# SPI_Backplane.net
KiCad netlist of a schematic drawn in EAGLE
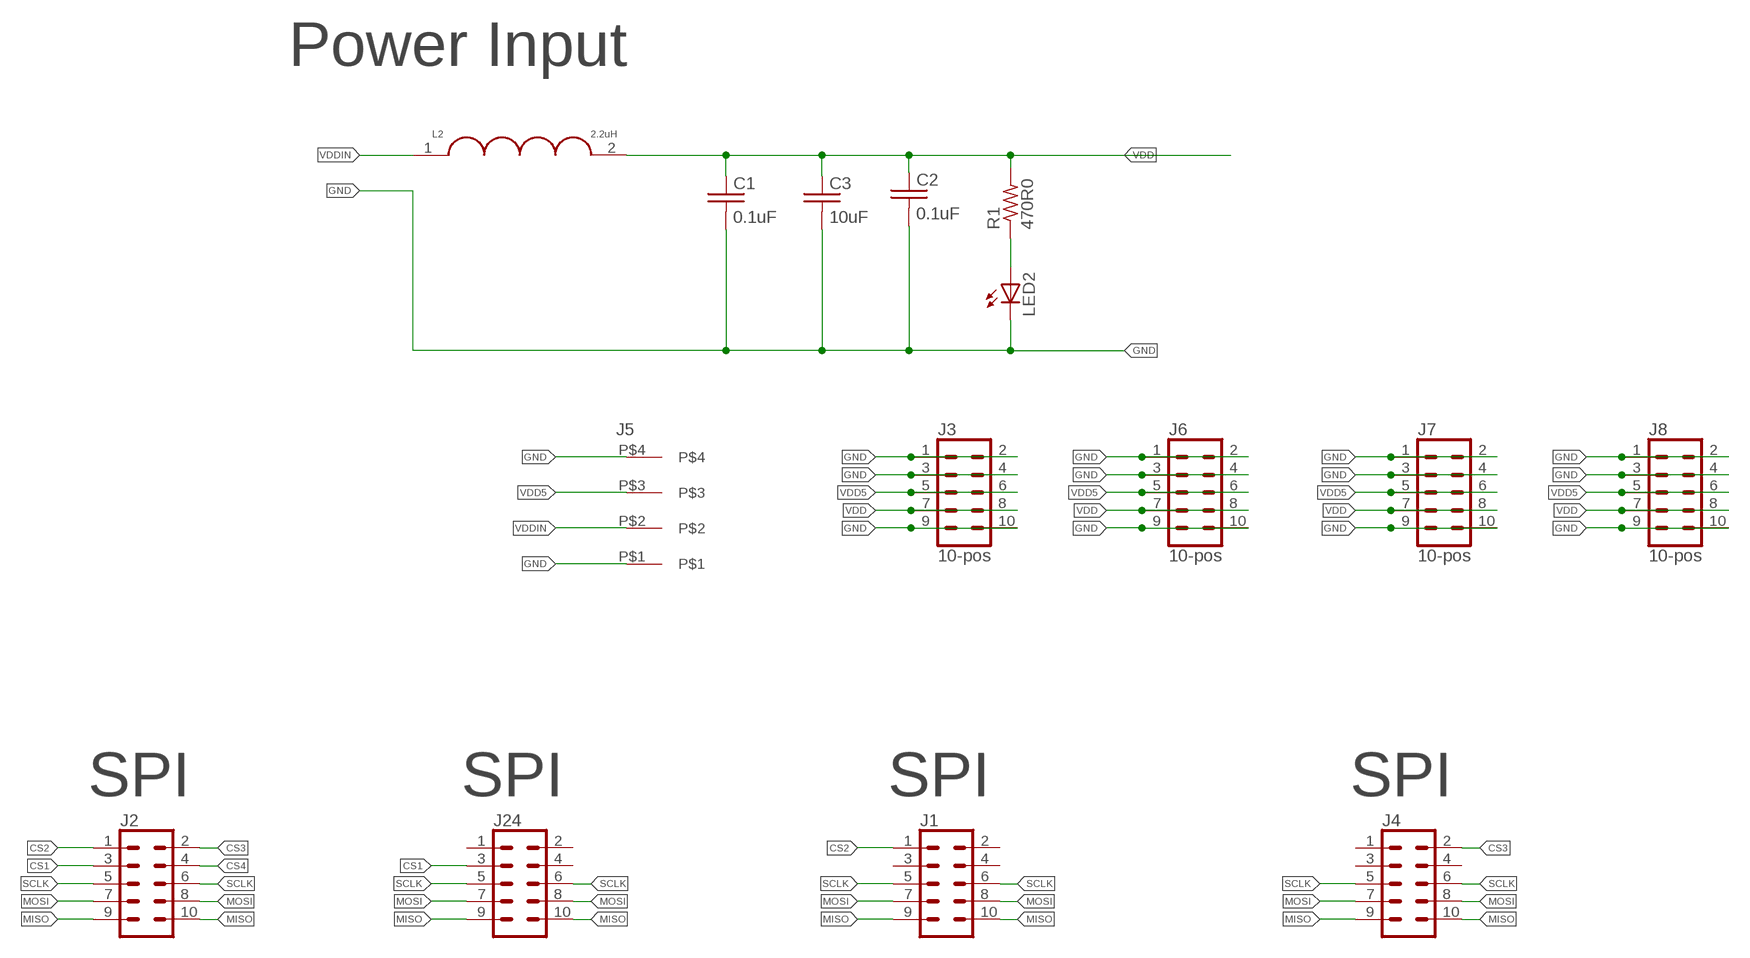
[diagram p0: schematic, sheet 1]

(export (version "E")
  (design (tool "Eeschema 10.0.6"))
  (components
    (comp (ref "C1")
      (value "0.1uF")
      (footprint "eagle-import:0402")
      (fields (field (name "PARTNO") "CL05F104ZO5NNNC"))
      (libsource (lib "eagle-import") (part "C_0402_0.1UF"))
    )
    (comp (ref "C2")
      (value "0.1uF")
      (footprint "eagle-import:0402")
      (fields (field (name "PARTNO") "CL05F104ZO5NNNC"))
      (libsource (lib "eagle-import") (part "C_0402_0.1UF"))
    )
    (comp (ref "C3")
      (value "10uF")
      (footprint "eagle-import:0402")
      (fields (field (name "PARTNO") "CL05A106MP8NUB8"))
      (libsource (lib "eagle-import") (part "C_0402_10UF"))
    )
    (comp (ref "J1")
      (value "CONN_05X2PTH")
      (footprint "eagle-import:2X5")
      (libsource (lib "eagle-import") (part "CONN_05X2PTH"))
    )
    (comp (ref "J2")
      (value "CONN_05X2PTH")
      (footprint "eagle-import:2X5")
      (libsource (lib "eagle-import") (part "CONN_05X2PTH"))
    )
    (comp (ref "J3")
      (value "10-pos")
      (footprint "eagle-import:2X5")
      (fields (field (name "PARTNO") "PH2RA-10-UA"))
      (libsource (lib "eagle-import") (part "CONN_05X2_RAPTH"))
    )
    (comp (ref "J4")
      (value "CONN_05X2PTH")
      (footprint "eagle-import:2X5")
      (libsource (lib "eagle-import") (part "CONN_05X2PTH"))
    )
    (comp (ref "J5")
      (value "4-pos")
      (footprint "eagle-import:1X4_3.81MM_PITCH")
      (fields (field (name "PARTNO") "691322310004"))
      (libsource (lib "eagle-import") (part "3.81MM_1_X_4_RT_ANGLE_PLUG_HEADER"))
    )
    (comp (ref "J6")
      (value "10-pos")
      (footprint "eagle-import:2X5")
      (fields (field (name "PARTNO") "PH2RA-10-UA"))
      (libsource (lib "eagle-import") (part "CONN_05X2_RAPTH"))
    )
    (comp (ref "J7")
      (value "10-pos")
      (footprint "eagle-import:2X5")
      (fields (field (name "PARTNO") "PH2RA-10-UA"))
      (libsource (lib "eagle-import") (part "CONN_05X2_RAPTH"))
    )
    (comp (ref "J8")
      (value "10-pos")
      (footprint "eagle-import:2X5")
      (fields (field (name "PARTNO") "PH2RA-10-UA"))
      (libsource (lib "eagle-import") (part "CONN_05X2_RAPTH"))
    )
    (comp (ref "J24")
      (value "CONN_05X2PTH")
      (footprint "eagle-import:2X5")
      (libsource (lib "eagle-import") (part "CONN_05X2PTH"))
    )
    (comp (ref "L2")
      (value "2.2uH")
      (footprint "eagle-import:1008")
      (fields (field (name "PARTNO") "LQM2HPN2R2MG0L"))
      (libsource (lib "eagle-import") (part "INDUCTOR_1008_2.2_MH_1.3A"))
    )
    (comp (ref "LED2")
      (value "Green")
      (footprint "eagle-import:0805")
      (fields (field (name "PARTNO") "LG R971-KN-1"))
      (libsource (lib "eagle-import") (part "LED_0805_GREEN"))
    )
    (comp (ref "R1")
      (value "470R0")
      (footprint "eagle-import:0402")
      (fields (field (name "PARTNO") "RMCF0402JT470R"))
      (libsource (lib "eagle-import") (part "R_0402_470R0"))
    )
  )
  (nets
    (net (code "1") (name "CS1") (class "Default")
      (node (ref "J2") (pin "3") (pinfunction "3_3") (pintype "passive"))
      (node (ref "J24") (pin "3") (pinfunction "3_3") (pintype "passive"))
    )
    (net (code "2") (name "CS2") (class "Default")
      (node (ref "J1") (pin "1") (pinfunction "1_1") (pintype "passive"))
      (node (ref "J2") (pin "1") (pinfunction "1_1") (pintype "passive"))
    )
    (net (code "3") (name "CS3") (class "Default")
      (node (ref "J2") (pin "2") (pinfunction "2_2") (pintype "passive"))
      (node (ref "J4") (pin "2") (pinfunction "2_2") (pintype "passive"))
    )
    (net (code "4") (name "CS4") (class "Default")
      (node (ref "J2") (pin "4") (pinfunction "4_4") (pintype "passive"))
    )
    (net (code "5") (name "GND") (class "Default")
      (node (ref "C1") (pin "P$2") (pinfunction "2_P$2") (pintype "passive"))
      (node (ref "C2") (pin "P$2") (pinfunction "2_P$2") (pintype "passive"))
      (node (ref "C3") (pin "P$2") (pinfunction "2_P$2") (pintype "passive"))
      (node (ref "J3") (pin "1") (pinfunction "1_1") (pintype "passive"))
      (node (ref "J3") (pin "10") (pinfunction "10_10") (pintype "passive"))
      (node (ref "J3") (pin "2") (pinfunction "2_2") (pintype "passive"))
      (node (ref "J3") (pin "3") (pinfunction "3_3") (pintype "passive"))
      (node (ref "J3") (pin "4") (pinfunction "4_4") (pintype "passive"))
      (node (ref "J3") (pin "9") (pinfunction "9_9") (pintype "passive"))
      (node (ref "J5") (pin "P$1") (pinfunction "P$1_P$1") (pintype "bidirectional"))
      (node (ref "J5") (pin "P$4") (pinfunction "P$4_P$4") (pintype "bidirectional"))
      (node (ref "J6") (pin "1") (pinfunction "1_1") (pintype "passive"))
      (node (ref "J6") (pin "10") (pinfunction "10_10") (pintype "passive"))
      (node (ref "J6") (pin "2") (pinfunction "2_2") (pintype "passive"))
      (node (ref "J6") (pin "3") (pinfunction "3_3") (pintype "passive"))
      (node (ref "J6") (pin "4") (pinfunction "4_4") (pintype "passive"))
      (node (ref "J6") (pin "9") (pinfunction "9_9") (pintype "passive"))
      (node (ref "J7") (pin "1") (pinfunction "1_1") (pintype "passive"))
      (node (ref "J7") (pin "10") (pinfunction "10_10") (pintype "passive"))
      (node (ref "J7") (pin "2") (pinfunction "2_2") (pintype "passive"))
      (node (ref "J7") (pin "3") (pinfunction "3_3") (pintype "passive"))
      (node (ref "J7") (pin "4") (pinfunction "4_4") (pintype "passive"))
      (node (ref "J7") (pin "9") (pinfunction "9_9") (pintype "passive"))
      (node (ref "J8") (pin "1") (pinfunction "1_1") (pintype "passive"))
      (node (ref "J8") (pin "10") (pinfunction "10_10") (pintype "passive"))
      (node (ref "J8") (pin "2") (pinfunction "2_2") (pintype "passive"))
      (node (ref "J8") (pin "3") (pinfunction "3_3") (pintype "passive"))
      (node (ref "J8") (pin "4") (pinfunction "4_4") (pintype "passive"))
      (node (ref "J8") (pin "9") (pinfunction "9_9") (pintype "passive"))
      (node (ref "LED2") (pin "2") (pinfunction "C_2") (pintype "passive"))
    )
    (net (code "6") (name "MISO") (class "Default")
      (node (ref "J1") (pin "10") (pinfunction "10_10") (pintype "passive"))
      (node (ref "J1") (pin "9") (pinfunction "9_9") (pintype "passive"))
      (node (ref "J2") (pin "10") (pinfunction "10_10") (pintype "passive"))
      (node (ref "J2") (pin "9") (pinfunction "9_9") (pintype "passive"))
      (node (ref "J24") (pin "10") (pinfunction "10_10") (pintype "passive"))
      (node (ref "J24") (pin "9") (pinfunction "9_9") (pintype "passive"))
      (node (ref "J4") (pin "10") (pinfunction "10_10") (pintype "passive"))
      (node (ref "J4") (pin "9") (pinfunction "9_9") (pintype "passive"))
    )
    (net (code "7") (name "MOSI") (class "Default")
      (node (ref "J1") (pin "7") (pinfunction "7_7") (pintype "passive"))
      (node (ref "J1") (pin "8") (pinfunction "8_8") (pintype "passive"))
      (node (ref "J2") (pin "7") (pinfunction "7_7") (pintype "passive"))
      (node (ref "J2") (pin "8") (pinfunction "8_8") (pintype "passive"))
      (node (ref "J24") (pin "7") (pinfunction "7_7") (pintype "passive"))
      (node (ref "J24") (pin "8") (pinfunction "8_8") (pintype "passive"))
      (node (ref "J4") (pin "7") (pinfunction "7_7") (pintype "passive"))
      (node (ref "J4") (pin "8") (pinfunction "8_8") (pintype "passive"))
    )
    (net (code "8") (name "Net-(LED2-A)") (class "Default")
      (node (ref "LED2") (pin "1") (pinfunction "A_1") (pintype "passive"))
      (node (ref "R1") (pin "P$1") (pinfunction "1_P$1") (pintype "passive"))
    )
    (net (code "9") (name "SCLK") (class "Default")
      (node (ref "J1") (pin "5") (pinfunction "5_5") (pintype "passive"))
      (node (ref "J1") (pin "6") (pinfunction "6_6") (pintype "passive"))
      (node (ref "J2") (pin "5") (pinfunction "5_5") (pintype "passive"))
      (node (ref "J2") (pin "6") (pinfunction "6_6") (pintype "passive"))
      (node (ref "J24") (pin "5") (pinfunction "5_5") (pintype "passive"))
      (node (ref "J24") (pin "6") (pinfunction "6_6") (pintype "passive"))
      (node (ref "J4") (pin "5") (pinfunction "5_5") (pintype "passive"))
      (node (ref "J4") (pin "6") (pinfunction "6_6") (pintype "passive"))
    )
    (net (code "10") (name "VDD") (class "Default")
      (node (ref "C1") (pin "P$1") (pinfunction "1_P$1") (pintype "passive"))
      (node (ref "C2") (pin "P$1") (pinfunction "1_P$1") (pintype "passive"))
      (node (ref "C3") (pin "P$1") (pinfunction "1_P$1") (pintype "passive"))
      (node (ref "J3") (pin "7") (pinfunction "7_7") (pintype "passive"))
      (node (ref "J3") (pin "8") (pinfunction "8_8") (pintype "passive"))
      (node (ref "J6") (pin "7") (pinfunction "7_7") (pintype "passive"))
      (node (ref "J6") (pin "8") (pinfunction "8_8") (pintype "passive"))
      (node (ref "J7") (pin "7") (pinfunction "7_7") (pintype "passive"))
      (node (ref "J7") (pin "8") (pinfunction "8_8") (pintype "passive"))
      (node (ref "J8") (pin "7") (pinfunction "7_7") (pintype "passive"))
      (node (ref "J8") (pin "8") (pinfunction "8_8") (pintype "passive"))
      (node (ref "L2") (pin "2") (pinfunction "P$2_2") (pintype "bidirectional"))
      (node (ref "R1") (pin "P$2") (pinfunction "2_P$2") (pintype "passive"))
    )
    (net (code "11") (name "VDD5") (class "Default")
      (node (ref "J3") (pin "5") (pinfunction "5_5") (pintype "passive"))
      (node (ref "J3") (pin "6") (pinfunction "6_6") (pintype "passive"))
      (node (ref "J5") (pin "P$3") (pinfunction "P$3_P$3") (pintype "bidirectional"))
      (node (ref "J6") (pin "5") (pinfunction "5_5") (pintype "passive"))
      (node (ref "J6") (pin "6") (pinfunction "6_6") (pintype "passive"))
      (node (ref "J7") (pin "5") (pinfunction "5_5") (pintype "passive"))
      (node (ref "J7") (pin "6") (pinfunction "6_6") (pintype "passive"))
      (node (ref "J8") (pin "5") (pinfunction "5_5") (pintype "passive"))
      (node (ref "J8") (pin "6") (pinfunction "6_6") (pintype "passive"))
    )
    (net (code "12") (name "VDDIN") (class "Default")
      (node (ref "J5") (pin "P$2") (pinfunction "P$2_P$2") (pintype "bidirectional"))
      (node (ref "L2") (pin "1") (pinfunction "P$1_1") (pintype "bidirectional"))
    )
    (net (code "13") (name "unconnected-(J1-Pad2)") (class "Default")
      (node (ref "J1") (pin "2") (pinfunction "2_2") (pintype "passive"))
    )
    (net (code "14") (name "unconnected-(J1-Pad3)") (class "Default")
      (node (ref "J1") (pin "3") (pinfunction "3_3") (pintype "passive"))
    )
    (net (code "15") (name "unconnected-(J1-Pad4)") (class "Default")
      (node (ref "J1") (pin "4") (pinfunction "4_4") (pintype "passive"))
    )
    (net (code "16") (name "unconnected-(J4-Pad1)") (class "Default")
      (node (ref "J4") (pin "1") (pinfunction "1_1") (pintype "passive"))
    )
    (net (code "17") (name "unconnected-(J4-Pad3)") (class "Default")
      (node (ref "J4") (pin "3") (pinfunction "3_3") (pintype "passive"))
    )
    (net (code "18") (name "unconnected-(J4-Pad4)") (class "Default")
      (node (ref "J4") (pin "4") (pinfunction "4_4") (pintype "passive"))
    )
    (net (code "19") (name "unconnected-(J24-Pad1)") (class "Default")
      (node (ref "J24") (pin "1") (pinfunction "1_1") (pintype "passive"))
    )
    (net (code "20") (name "unconnected-(J24-Pad2)") (class "Default")
      (node (ref "J24") (pin "2") (pinfunction "2_2") (pintype "passive"))
    )
    (net (code "21") (name "unconnected-(J24-Pad4)") (class "Default")
      (node (ref "J24") (pin "4") (pinfunction "4_4") (pintype "passive"))
    )
  )
)
